# 1_3.net
KiCad netlist of a schematic drawn in Altium Designer
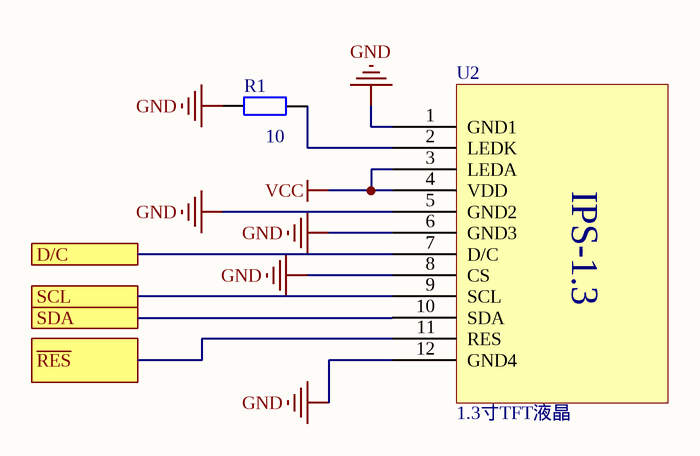
[diagram p0: 1.3英寸液晶电路.SchDoc]

(export (version "E")
  (design (tool "Eeschema 10.0.6"))
  (components
    (comp (ref "R1")
      (value "10")
      (footprint "6-0805_N")
      (description "Resistor")
      (fields (field (name "Comment") "Res2") (field (name "PUBLISHER") "Altium Limited"))
      (libsource (lib "基于SMT32的DDS信号源原理图库") (part "Res2"))
    )
    (comp (ref "U2")
      (value "1.3寸TFT液晶")
      (footprint "1.3-TFT-TPS")
      (libsource (lib "基于SMT32的DDS信号源原理图库") (part "1.3寸TFT液晶"))
    )
  )
  (nets
    (net (code "1") (name "/D{slash}C") (class "Default")
      (node (ref "U2") (pin "7") (pinfunction "D/C_7") (pintype "passive"))
    )
    (net (code "2") (name "/SCL") (class "Default")
      (node (ref "U2") (pin "9") (pinfunction "SCL_9") (pintype "passive"))
    )
    (net (code "3") (name "/SDA") (class "Default")
      (node (ref "U2") (pin "10") (pinfunction "SDA_10") (pintype "passive"))
    )
    (net (code "4") (name "/~{RES}") (class "Default")
      (node (ref "U2") (pin "11") (pinfunction "RES_11") (pintype "passive"))
    )
    (net (code "5") (name "GND") (class "Default")
      (node (ref "R1") (pin "1") (pinfunction "1_1") (pintype "passive"))
      (node (ref "U2") (pin "1") (pinfunction "GND1_1") (pintype "passive"))
      (node (ref "U2") (pin "12") (pinfunction "GND4_12") (pintype "passive"))
      (node (ref "U2") (pin "5") (pinfunction "GND2_5") (pintype "passive"))
      (node (ref "U2") (pin "6") (pinfunction "GND3_6") (pintype "passive"))
      (node (ref "U2") (pin "8") (pinfunction "CS_8") (pintype "passive"))
    )
    (net (code "6") (name "Net-(U2-LEDK)") (class "Default")
      (node (ref "R1") (pin "2") (pinfunction "2_2") (pintype "passive"))
      (node (ref "U2") (pin "2") (pinfunction "LEDK_2") (pintype "passive"))
    )
    (net (code "7") (name "VCC") (class "Default")
      (node (ref "U2") (pin "3") (pinfunction "LEDA_3") (pintype "passive"))
      (node (ref "U2") (pin "4") (pinfunction "VDD_4") (pintype "passive"))
    )
  )
)
